# BreadBoardPS_604.net
KiCad netlist of a schematic drawn in EAGLE
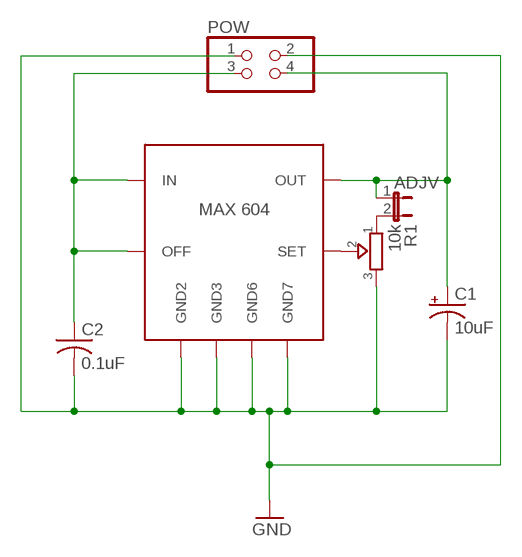
[diagram p0: schematic, sheet 1]

(export (version "E")
  (design (tool "Eeschema 10.0.6"))
  (components
    (comp (ref "ADJV")
      (value "JP1E")
      (footprint "eagle-import:JP1")
      (libsource (lib "eagle-import") (part "JP1E"))
    )
    (comp (ref "C1")
      (value "10uF")
      (footprint "eagle-import:E2,5-5")
      (libsource (lib "eagle-import") (part "CPOL-USE2.5-5"))
    )
    (comp (ref "C2")
      (value "0.1uF")
      (footprint "eagle-import:C025-024X044")
      (libsource (lib "eagle-import") (part "C-US025-024X044"))
    )
    (comp (ref "MAX604")
      (value "MAX604")
      (footprint "eagle-import:DIL08")
      (libsource (lib "eagle-import") (part "MAX604"))
    )
    (comp (ref "POW")
      (value "PINHD-2X22X02/90NOSILK")
      (footprint "eagle-import:2X02_90")
      (libsource (lib "eagle-import") (part "PINHD-2X22X02/90NOSILK"))
    )
    (comp (ref "R1")
      (value "10k")
      (footprint "eagle-import:TRIMMER_3306F")
      (libsource (lib "eagle-import") (part "TRIMMER-3306F"))
    )
  )
  (nets
    (net (code "1") (name "GND") (class "Default")
      (node (ref "C1") (pin "-") (pinfunction "-_-") (pintype "passive"))
      (node (ref "C2") (pin "2") (pinfunction "2_2") (pintype "passive"))
      (node (ref "MAX604") (pin "2") (pinfunction "GND2_2") (pintype "bidirectional"))
      (node (ref "MAX604") (pin "3") (pinfunction "GND3_3") (pintype "bidirectional"))
      (node (ref "MAX604") (pin "6") (pinfunction "GND6_6") (pintype "bidirectional"))
      (node (ref "MAX604") (pin "7") (pinfunction "GND7_7") (pintype "bidirectional"))
      (node (ref "POW") (pin "1") (pinfunction "1_1") (pintype "passive"))
      (node (ref "POW") (pin "2") (pinfunction "2_2") (pintype "passive"))
      (node (ref "R1") (pin "3") (pinfunction "3_3") (pintype "passive"))
    )
    (net (code "2") (name "Net-(ADJV-Pad2)") (class "Default")
      (node (ref "ADJV") (pin "2") (pinfunction "2_2") (pintype "passive"))
      (node (ref "R1") (pin "1") (pinfunction "1_1") (pintype "passive"))
    )
    (net (code "3") (name "Net-(MAX604-IN)") (class "Default")
      (node (ref "C2") (pin "1") (pinfunction "1_1") (pintype "passive"))
      (node (ref "MAX604") (pin "1") (pinfunction "IN_1") (pintype "bidirectional"))
      (node (ref "MAX604") (pin "4") (pinfunction "OFF_4") (pintype "bidirectional"))
      (node (ref "POW") (pin "3") (pinfunction "3_3") (pintype "passive"))
    )
    (net (code "4") (name "Net-(MAX604-OUT)") (class "Default")
      (node (ref "ADJV") (pin "1") (pinfunction "1_1") (pintype "passive"))
      (node (ref "C1") (pin "+") (pinfunction "+_+") (pintype "passive"))
      (node (ref "MAX604") (pin "8") (pinfunction "OUT_8") (pintype "bidirectional"))
      (node (ref "POW") (pin "4") (pinfunction "4_4") (pintype "passive"))
    )
    (net (code "5") (name "Net-(MAX604-SET)") (class "Default")
      (node (ref "MAX604") (pin "5") (pinfunction "SET_5") (pintype "bidirectional"))
      (node (ref "R1") (pin "2") (pinfunction "2_2") (pintype "passive"))
    )
  )
)
